# STl-Link-V200.net
KiCad netlist of a schematic drawn in EAGLE
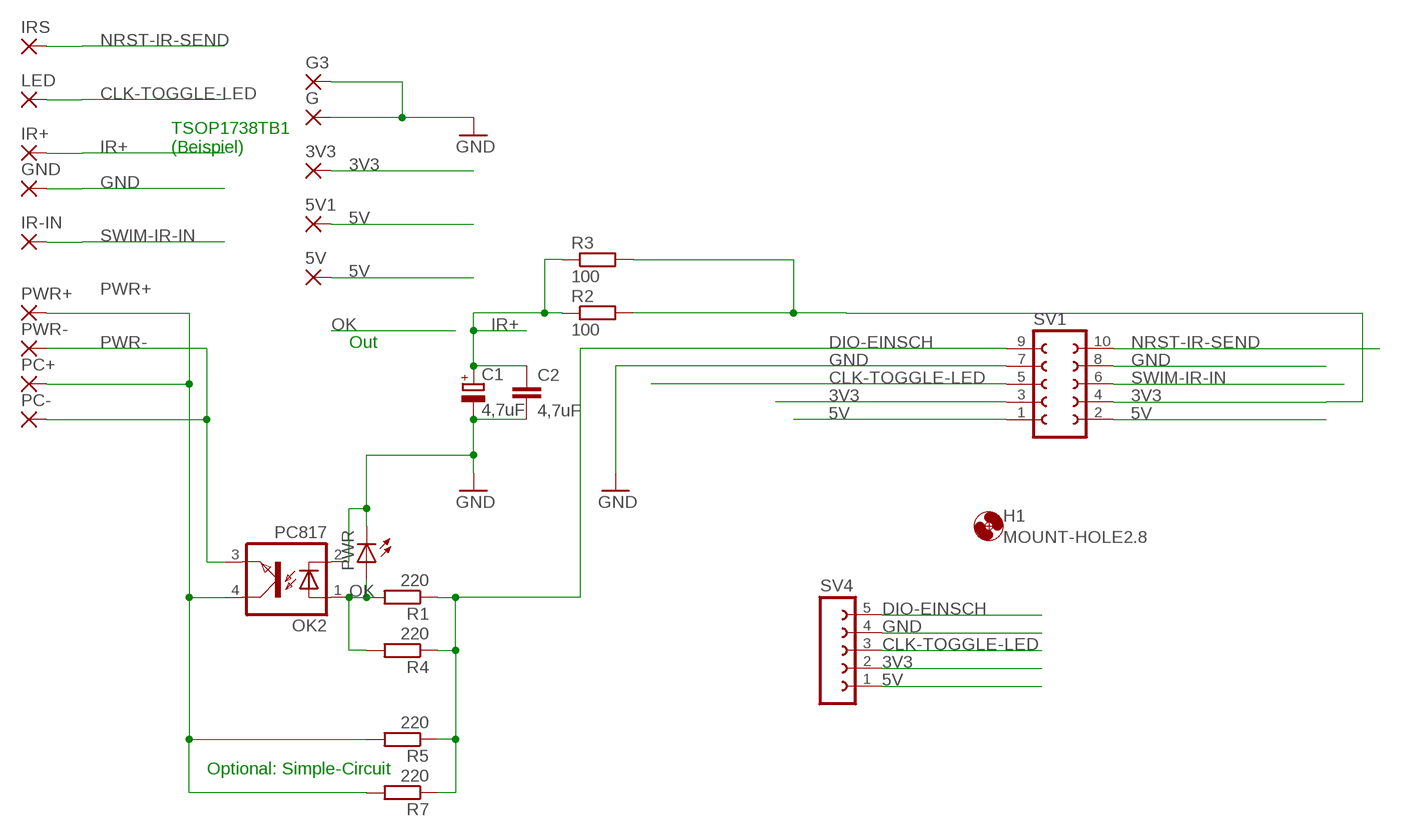
[diagram p0: schematic, sheet 1]

(export (version "E")
  (design (tool "Eeschema 10.0.6"))
  (components
    (comp (ref "3V3")
      (value "SMD2")
      (footprint "eagle-import:SMD1,27-2,54")
      (libsource (lib "eagle-import") (part "SMD2"))
    )
    (comp (ref "5V")
      (value "SMD2")
      (footprint "eagle-import:SMD1,27-2,54")
      (libsource (lib "eagle-import") (part "SMD2"))
    )
    (comp (ref "5V1")
      (value "SMD2")
      (footprint "eagle-import:SMD1,27-2,54")
      (libsource (lib "eagle-import") (part "SMD2"))
    )
    (comp (ref "C1")
      (value "4,7uF")
      (footprint "eagle-import:E1,8-4")
      (libsource (lib "eagle-import") (part "CPOL-EUE1.8-4"))
    )
    (comp (ref "C2")
      (value "4,7uF")
      (footprint "eagle-import:C1206K")
      (libsource (lib "eagle-import") (part "C-EUC1206K"))
    )
    (comp (ref "G")
      (value "SMD2")
      (footprint "eagle-import:SMD1,27-2,54")
      (libsource (lib "eagle-import") (part "SMD2"))
    )
    (comp (ref "G3")
      (value "SMD2")
      (footprint "eagle-import:SMD1,27-2,54")
      (libsource (lib "eagle-import") (part "SMD2"))
    )
    (comp (ref "GND")
      (value "SMD2")
      (footprint "eagle-import:SMD1,27-2,54")
      (libsource (lib "eagle-import") (part "SMD2"))
    )
    (comp (ref "H1")
      (value "MOUNT-HOLE2.8")
      (footprint "eagle-import:2,8")
      (libsource (lib "eagle-import") (part "MOUNT-HOLE2.8"))
    )
    (comp (ref "IR+")
      (value "SMD2")
      (footprint "eagle-import:SMD1,27-2,54")
      (libsource (lib "eagle-import") (part "SMD2"))
    )
    (comp (ref "IR-IN")
      (value "SMD2")
      (footprint "eagle-import:SMD1,27-2,54")
      (libsource (lib "eagle-import") (part "SMD2"))
    )
    (comp (ref "IRS")
      (value "SMD2")
      (footprint "eagle-import:SMD1,27-2,54")
      (libsource (lib "eagle-import") (part "SMD2"))
    )
    (comp (ref "LED")
      (value "SMD2")
      (footprint "eagle-import:SMD1,27-2,54")
      (libsource (lib "eagle-import") (part "SMD2"))
    )
    (comp (ref "OK2")
      (value "PC817")
      (footprint "eagle-import:DIL04")
      (fields (field (name "MPN") "PC817X4J000F"))
      (libsource (lib "eagle-import") (part "PC817"))
    )
    (comp (ref "PC+")
      (value "SMD2")
      (footprint "eagle-import:SMD1,27-2,54")
      (libsource (lib "eagle-import") (part "SMD2"))
    )
    (comp (ref "PC-")
      (value "SMD2")
      (footprint "eagle-import:SMD1,27-2,54")
      (libsource (lib "eagle-import") (part "SMD2"))
    )
    (comp (ref "PWR")
      (value "LEDCHIPLED_1206")
      (footprint "eagle-import:CHIPLED_1206")
      (libsource (lib "eagle-import") (part "LEDCHIPLED_1206"))
    )
    (comp (ref "PWR+")
      (value "SMD2")
      (footprint "eagle-import:SMD1,27-2,54")
      (libsource (lib "eagle-import") (part "SMD2"))
    )
    (comp (ref "PWR-")
      (value "SMD2")
      (footprint "eagle-import:SMD1,27-2,54")
      (libsource (lib "eagle-import") (part "SMD2"))
    )
    (comp (ref "R1")
      (value "220")
      (footprint "eagle-import:0204_7")
      (libsource (lib "eagle-import") (part "R-EU_0204/7"))
    )
    (comp (ref "R2")
      (value "100")
      (footprint "eagle-import:0204_7")
      (libsource (lib "eagle-import") (part "R-EU_0204/7"))
    )
    (comp (ref "R3")
      (value "100")
      (footprint "eagle-import:R0805W")
      (libsource (lib "eagle-import") (part "R-EU_R0805W"))
    )
    (comp (ref "R4")
      (value "220")
      (footprint "eagle-import:R0805W")
      (libsource (lib "eagle-import") (part "R-EU_R0805W"))
    )
    (comp (ref "R5")
      (value "220")
      (footprint "eagle-import:0204_7")
      (libsource (lib "eagle-import") (part "R-EU_0204/7"))
    )
    (comp (ref "R7")
      (value "220")
      (footprint "eagle-import:R0805W")
      (libsource (lib "eagle-import") (part "R-EU_R0805W"))
    )
    (comp (ref "SV1")
      (value "FE05-2")
      (footprint "eagle-import:FE05-2")
      (libsource (lib "eagle-import") (part "FE05-2"))
    )
    (comp (ref "SV4")
      (value "FE05-1")
      (footprint "eagle-import:FE05-1")
      (libsource (lib "eagle-import") (part "FE05-1"))
    )
  )
  (nets
    (net (code "1") (name "/3V3") (class "Default")
      (node (ref "3V3") (pin "1") (pinfunction "P_1") (pintype "passive"))
      (node (ref "R2") (pin "2") (pinfunction "2_2") (pintype "passive"))
      (node (ref "R3") (pin "2") (pinfunction "2_2") (pintype "passive"))
      (node (ref "SV1") (pin "3") (pinfunction "3_3") (pintype "passive"))
      (node (ref "SV1") (pin "4") (pinfunction "4_4") (pintype "passive"))
      (node (ref "SV4") (pin "2") (pinfunction "2_2") (pintype "passive"))
    )
    (net (code "2") (name "/5V") (class "Default")
      (node (ref "5V") (pin "1") (pinfunction "P_1") (pintype "passive"))
      (node (ref "5V1") (pin "1") (pinfunction "P_1") (pintype "passive"))
      (node (ref "SV1") (pin "1") (pinfunction "1_1") (pintype "passive"))
      (node (ref "SV1") (pin "2") (pinfunction "2_2") (pintype "passive"))
      (node (ref "SV4") (pin "1") (pinfunction "1_1") (pintype "passive"))
    )
    (net (code "3") (name "/CLK-TOGGLE-LED") (class "Default")
      (node (ref "LED") (pin "1") (pinfunction "P_1") (pintype "passive"))
      (node (ref "SV1") (pin "5") (pinfunction "5_5") (pintype "passive"))
      (node (ref "SV4") (pin "3") (pinfunction "3_3") (pintype "passive"))
    )
    (net (code "4") (name "/DIO-EINSCH") (class "Default")
      (node (ref "R1") (pin "1") (pinfunction "1_1") (pintype "passive"))
      (node (ref "R4") (pin "1") (pinfunction "1_1") (pintype "passive"))
      (node (ref "R5") (pin "1") (pinfunction "1_1") (pintype "passive"))
      (node (ref "R7") (pin "1") (pinfunction "1_1") (pintype "passive"))
      (node (ref "SV1") (pin "9") (pinfunction "9_9") (pintype "passive"))
      (node (ref "SV4") (pin "5") (pinfunction "5_5") (pintype "passive"))
    )
    (net (code "5") (name "/IR+") (class "Default")
      (node (ref "C1") (pin "+") (pinfunction "+_+") (pintype "passive"))
      (node (ref "C2") (pin "1") (pinfunction "1_1") (pintype "passive"))
      (node (ref "IR+") (pin "1") (pinfunction "P_1") (pintype "passive"))
      (node (ref "R2") (pin "1") (pinfunction "1_1") (pintype "passive"))
      (node (ref "R3") (pin "1") (pinfunction "1_1") (pintype "passive"))
    )
    (net (code "6") (name "/NRST-IR-SEND") (class "Default")
      (node (ref "IRS") (pin "1") (pinfunction "P_1") (pintype "passive"))
      (node (ref "SV1") (pin "10") (pinfunction "10_10") (pintype "passive"))
    )
    (net (code "7") (name "/OK") (class "Default")
      (node (ref "OK2") (pin "1") (pinfunction "A_1") (pintype "passive"))
      (node (ref "PWR") (pin "A") (pinfunction "A_A") (pintype "passive"))
      (node (ref "R1") (pin "2") (pinfunction "2_2") (pintype "passive"))
      (node (ref "R4") (pin "2") (pinfunction "2_2") (pintype "passive"))
    )
    (net (code "8") (name "/PWR+") (class "Default")
      (node (ref "OK2") (pin "4") (pinfunction "COL_4") (pintype "passive"))
      (node (ref "PC+") (pin "1") (pinfunction "P_1") (pintype "passive"))
      (node (ref "PWR+") (pin "1") (pinfunction "P_1") (pintype "passive"))
      (node (ref "R5") (pin "2") (pinfunction "2_2") (pintype "passive"))
      (node (ref "R7") (pin "2") (pinfunction "2_2") (pintype "passive"))
    )
    (net (code "9") (name "/PWR-") (class "Default")
      (node (ref "OK2") (pin "3") (pinfunction "EMIT_3") (pintype "passive"))
      (node (ref "PC-") (pin "1") (pinfunction "P_1") (pintype "passive"))
      (node (ref "PWR-") (pin "1") (pinfunction "P_1") (pintype "passive"))
    )
    (net (code "10") (name "/SWIM-IR-IN") (class "Default")
      (node (ref "IR-IN") (pin "1") (pinfunction "P_1") (pintype "passive"))
      (node (ref "SV1") (pin "6") (pinfunction "6_6") (pintype "passive"))
    )
    (net (code "11") (name "GND") (class "Default")
      (node (ref "C1") (pin "-") (pinfunction "-_-") (pintype "passive"))
      (node (ref "C2") (pin "2") (pinfunction "2_2") (pintype "passive"))
      (node (ref "G") (pin "1") (pinfunction "P_1") (pintype "passive"))
      (node (ref "G3") (pin "1") (pinfunction "P_1") (pintype "passive"))
      (node (ref "GND") (pin "1") (pinfunction "P_1") (pintype "passive"))
      (node (ref "OK2") (pin "2") (pinfunction "C_2") (pintype "passive"))
      (node (ref "PWR") (pin "C") (pinfunction "C_C") (pintype "passive"))
      (node (ref "SV1") (pin "7") (pinfunction "7_7") (pintype "passive"))
      (node (ref "SV1") (pin "8") (pinfunction "8_8") (pintype "passive"))
      (node (ref "SV4") (pin "4") (pinfunction "4_4") (pintype "passive"))
    )
  )
)
